# remote-digital-liquid-sensor.net
KiCad netlist of a schematic drawn in EasyEDA
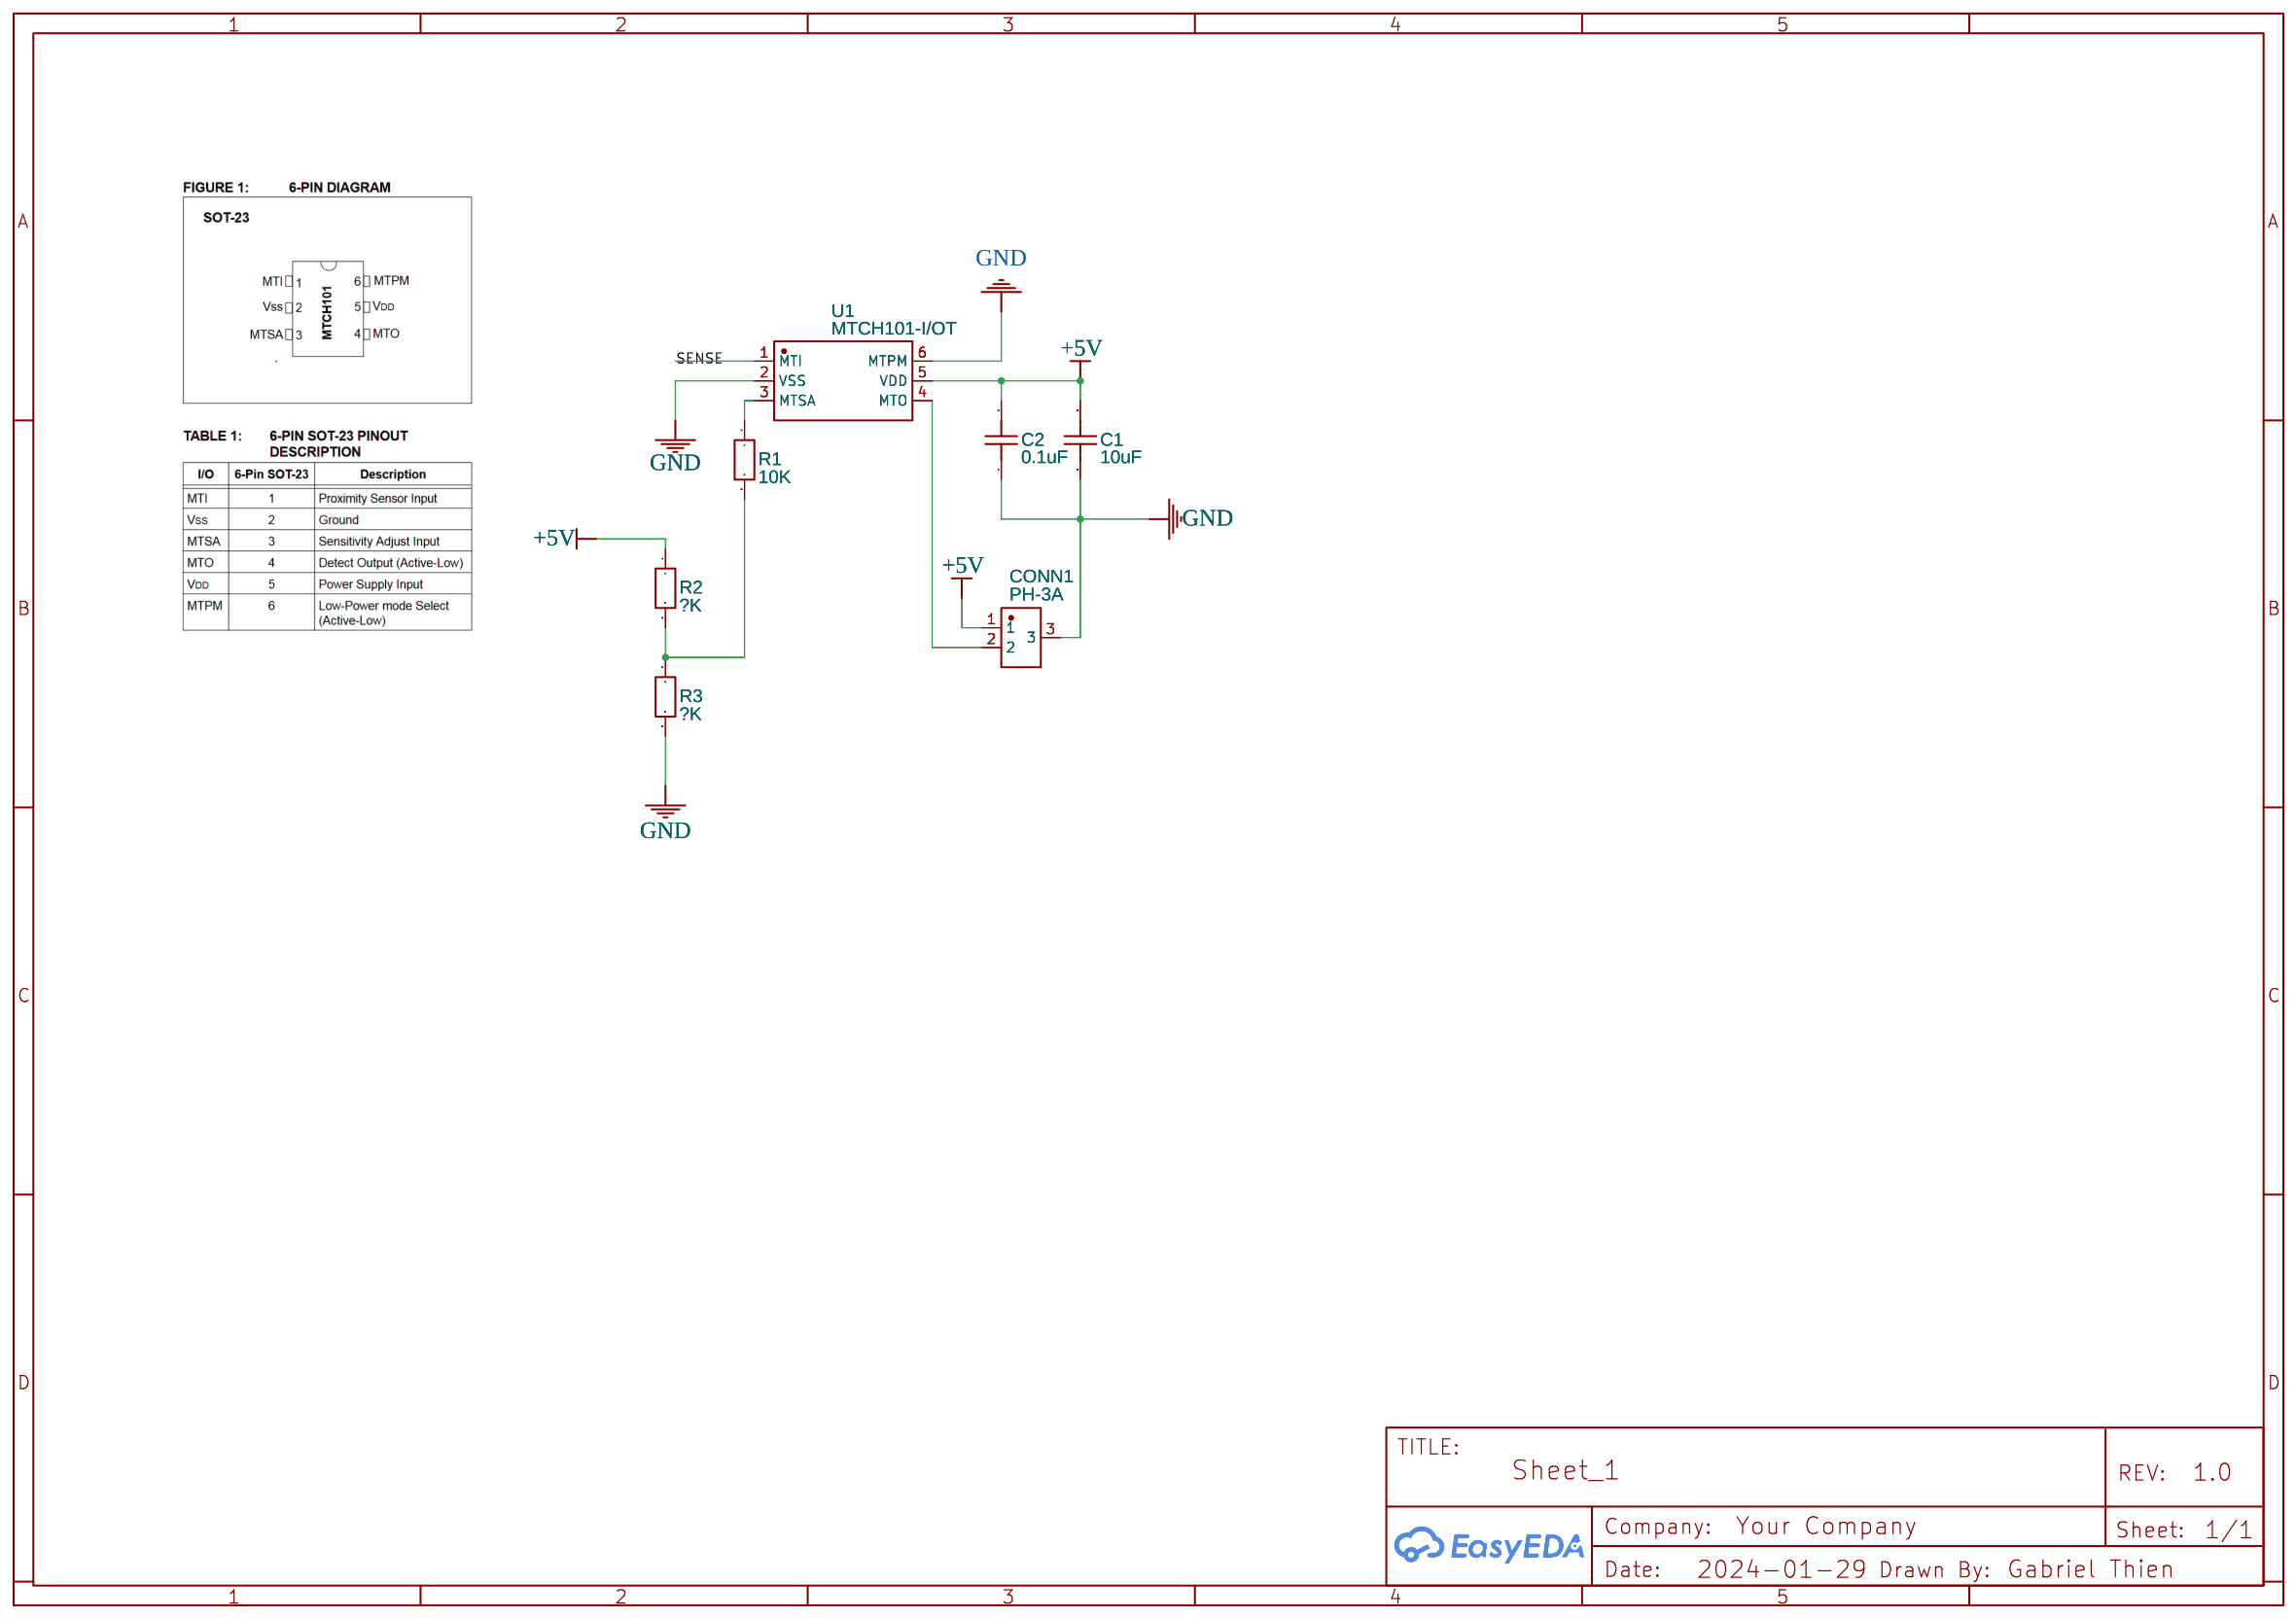
[diagram p0: schematic sheet]

(export (version "E")
  (design (tool "Eeschema 10.0.6"))
  (components
    (comp (ref "C1") (value "10uF") (libsource (lib "") (part "C_0603_US")))
    (comp (ref "C2") (value "0.1uF") (libsource (lib "") (part "C_0603_US")))
    (comp (ref "CONN1")
      (value "PH-3A")
      (fields (field (name "Manufacturer Part") "PH-3A/红色"))
      (libsource (lib "") (part "PH-3A/红色"))
    )
    (comp (ref "R1") (value "10K") (libsource (lib "") (part "R_0603_EU")))
    (comp (ref "R2") (value "?K") (libsource (lib "") (part "R_0603_EU")))
    (comp (ref "R3") (value "?K") (libsource (lib "") (part "R_0603_EU")))
    (comp (ref "U1")
      (value "MTCH101-I/OT")
      (fields (field (name "Manufacturer") "MICROCHIP(美国微芯)"))
      (libsource (lib "") (part "MTCH101-I/OT"))
    )
  )
  (nets
    (net (code "1") (name "+5V") (class "Default")
      (node (ref "C1") (pin "2") (pinfunction "2_2") (pintype "unspecified"))
      (node (ref "C2") (pin "2") (pinfunction "2_2") (pintype "unspecified"))
      (node (ref "CONN1") (pin "1") (pinfunction "1_1") (pintype "unspecified"))
      (node (ref "R2") (pin "1") (pinfunction "1_1") (pintype "unspecified"))
      (node (ref "U1") (pin "5") (pinfunction "VDD_5") (pintype "unspecified"))
    )
    (net (code "2") (name "/SENSE") (class "Default")
      (node (ref "U1") (pin "1") (pinfunction "MTI_1") (pintype "unspecified"))
    )
    (net (code "3") (name "GND") (class "Default")
      (node (ref "C1") (pin "1") (pinfunction "1_1") (pintype "unspecified"))
      (node (ref "C2") (pin "1") (pinfunction "1_1") (pintype "unspecified"))
      (node (ref "CONN1") (pin "3") (pinfunction "3_3") (pintype "unspecified"))
      (node (ref "R3") (pin "2") (pinfunction "2_2") (pintype "unspecified"))
      (node (ref "U1") (pin "2") (pinfunction "VSS_2") (pintype "unspecified"))
      (node (ref "U1") (pin "6") (pinfunction "MTPM_6") (pintype "unspecified"))
    )
    (net (code "4") (name "Net-(R1-Pad2)") (class "Default")
      (node (ref "R1") (pin "2") (pinfunction "2_2") (pintype "unspecified"))
      (node (ref "R2") (pin "2") (pinfunction "2_2") (pintype "unspecified"))
      (node (ref "R3") (pin "1") (pinfunction "1_1") (pintype "unspecified"))
    )
    (net (code "5") (name "Net-(U1-MTO)") (class "Default")
      (node (ref "CONN1") (pin "2") (pinfunction "2_2") (pintype "unspecified"))
      (node (ref "U1") (pin "4") (pinfunction "MTO_4") (pintype "unspecified"))
    )
    (net (code "6") (name "Net-(U1-MTSA)") (class "Default")
      (node (ref "R1") (pin "1") (pinfunction "1_1") (pintype "unspecified"))
      (node (ref "U1") (pin "3") (pinfunction "MTSA_3") (pintype "unspecified"))
    )
  )
)
